# ST_LINK_V2-1.net
KiCad netlist of a schematic drawn in Altium Designer
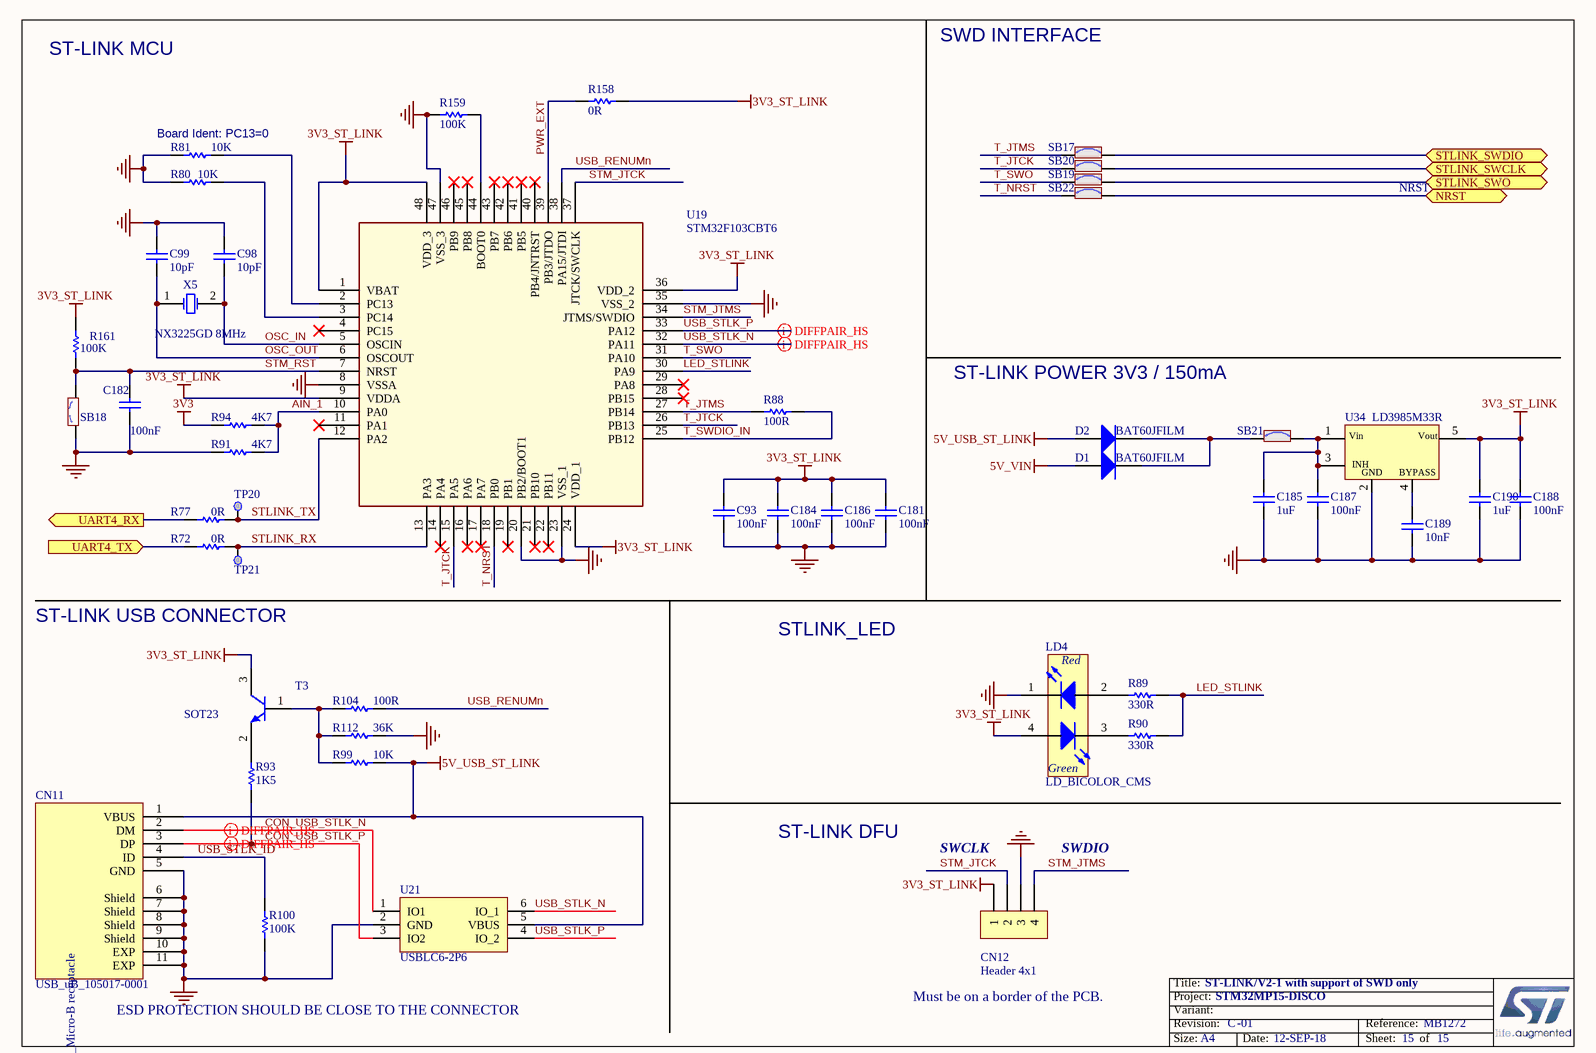
[diagram p0: ST_LINK_V2-1.SCHDOC]

(export (version "E")
  (design (tool "Eeschema 10.0.6"))
  (components
    (comp (ref "C93")
      (value "100nF")
      (footprint "C0402")
      (description "Capacitor,100nF,16V,X7R,10%,0402")
      (fields
        (field (name "INTERNAL_PART_NUMBER") "MCD-00006")
        (field (name "MANUFACTURER_PART_NUMBER") "CC0402KRX7R7BB104")
        (field (name "PROVIDED_BY") "SUBCO")
      )
      (libsource (lib "MCD_PARTS_database") (part "Capacitor"))
    )
    (comp (ref "C98")
      (value "10pF")
      (footprint "C0402")
      (description "Capacitor,10pF,50V,NPO,5%,0402")
      (fields
        (field (name "INTERNAL_PART_NUMBER") "MCD-00015")
        (field (name "MANUFACTURER_PART_NUMBER") "CC0402JRNPO9BN100")
        (field (name "PROVIDED_BY") "SUBCO")
      )
      (libsource (lib "MCD_PARTS_database") (part "Capacitor"))
    )
    (comp (ref "C99")
      (value "10pF")
      (footprint "C0402")
      (description "Capacitor,10pF,50V,NPO,5%,0402")
      (fields
        (field (name "INTERNAL_PART_NUMBER") "MCD-00015")
        (field (name "MANUFACTURER_PART_NUMBER") "CC0402JRNPO9BN100")
        (field (name "PROVIDED_BY") "SUBCO")
      )
      (libsource (lib "MCD_PARTS_database") (part "Capacitor"))
    )
    (comp (ref "C181")
      (value "100nF")
      (footprint "C0402")
      (description "Capacitor,100nF,16V,X7R,10%,0402")
      (fields
        (field (name "INTERNAL_PART_NUMBER") "MCD-00006")
        (field (name "MANUFACTURER_PART_NUMBER") "CC0402KRX7R7BB104")
        (field (name "PROVIDED_BY") "SUBCO")
      )
      (libsource (lib "MCD_PARTS_database") (part "Capacitor"))
    )
    (comp (ref "C182")
      (value "100nF")
      (footprint "C0402")
      (description "Capacitor,100nF,16V,X7R,10%,0402")
      (fields
        (field (name "INTERNAL_PART_NUMBER") "MCD-00006")
        (field (name "MANUFACTURER_PART_NUMBER") "CC0402KRX7R7BB104")
        (field (name "PROVIDED_BY") "SUBCO")
      )
      (libsource (lib "MCD_PARTS_database") (part "Capacitor"))
    )
    (comp (ref "C184")
      (value "100nF")
      (footprint "C0402")
      (description "Capacitor,100nF,16V,X7R,10%,0402")
      (fields
        (field (name "INTERNAL_PART_NUMBER") "MCD-00006")
        (field (name "MANUFACTURER_PART_NUMBER") "CC0402KRX7R7BB104")
        (field (name "PROVIDED_BY") "SUBCO")
      )
      (libsource (lib "MCD_PARTS_database") (part "Capacitor"))
    )
    (comp (ref "C185")
      (value "1uF")
      (footprint "C0603")
      (description "Capacitor,1uF,6V3,X5R,10%,0603")
      (fields
        (field (name "INTERNAL_PART_NUMBER") "MCD-00238")
        (field (name "MANUFACTURER_PART_NUMBER") "CC0603KRX5R5BB105")
        (field (name "PROVIDED_BY") "SUBCO")
      )
      (libsource (lib "MCD_PARTS_database") (part "Capacitor"))
    )
    (comp (ref "C186")
      (value "100nF")
      (footprint "C0402")
      (description "Capacitor,100nF,16V,X7R,10%,0402")
      (fields
        (field (name "INTERNAL_PART_NUMBER") "MCD-00006")
        (field (name "MANUFACTURER_PART_NUMBER") "CC0402KRX7R7BB104")
        (field (name "PROVIDED_BY") "SUBCO")
      )
      (libsource (lib "MCD_PARTS_database") (part "Capacitor"))
    )
    (comp (ref "C187")
      (value "100nF")
      (footprint "C0402")
      (description "Capacitor,100nF,16V,X7R,10%,0402")
      (fields
        (field (name "INTERNAL_PART_NUMBER") "MCD-00006")
        (field (name "MANUFACTURER_PART_NUMBER") "CC0402KRX7R7BB104")
        (field (name "PROVIDED_BY") "SUBCO")
      )
      (libsource (lib "MCD_PARTS_database") (part "Capacitor"))
    )
    (comp (ref "C188")
      (value "100nF")
      (footprint "C0402")
      (description "Capacitor,100nF,16V,X7R,10%,0402")
      (fields
        (field (name "INTERNAL_PART_NUMBER") "MCD-00006")
        (field (name "MANUFACTURER_PART_NUMBER") "CC0402KRX7R7BB104")
        (field (name "PROVIDED_BY") "SUBCO")
      )
      (libsource (lib "MCD_PARTS_database") (part "Capacitor"))
    )
    (comp (ref "C189")
      (value "10nF")
      (footprint "C0402")
      (description "Capacitor,10nF,16V,X7R,10%,0402")
      (fields
        (field (name "INTERNAL_PART_NUMBER") "MCD-00011")
        (field (name "MANUFACTURER_PART_NUMBER") "CC0402KRX7R7BB103")
        (field (name "PROVIDED_BY") "SUBCO")
      )
      (libsource (lib "MCD_PARTS_database") (part "Capacitor"))
    )
    (comp (ref "C190")
      (value "1uF")
      (footprint "C0603")
      (description "Capacitor,1uF,6V3,X5R,10%,0603")
      (fields
        (field (name "INTERNAL_PART_NUMBER") "MCD-00238")
        (field (name "MANUFACTURER_PART_NUMBER") "CC0603KRX5R5BB105")
        (field (name "PROVIDED_BY") "SUBCO")
      )
      (libsource (lib "MCD_PARTS_database") (part "Capacitor"))
    )
    (comp (ref "CN11")
      (value "USB_uB_105017-0001")
      (footprint "CON_USBMICROB_MOLEX_105017-0001_H2P90")
      (description "USB-MICRO-B, 0.65mm, RA, SMT, Bottom Mount,")
      (fields
        (field (name "INTERNAL_PART_NUMBER") "MCD-00028")
        (field (name "MANUFACTURER_PART_NUMBER") "1050170001")
        (field (name "PROVIDED_BY") "SUBCO")
      )
      (libsource (lib "MCD_PARTS_database") (part "USB_uB_105017.0001"))
    )
    (comp (ref "CN12")
      (value "Header 4x1")
      (footprint "CON_SAMTEC_TSW-104-07-G-S")
      (description "Header, 4x1, 2,54mm, VR, TH, Height 5.84mm/2.54mm")
      (fields
        (field (name "INTERNAL_PART_NUMBER") "MCD-00029")
        (field (name "MANUFACTURER_PART_NUMBER") "TSW-104-07-x-S")
        (field (name "PROVIDED_BY") "SUBCO")
      )
      (libsource (lib "MCD_PARTS_database") (part "Header 4x1"))
    )
    (comp (ref "D1")
      (value "BAT60JFILM")
      (footprint "DIO_SOD323")
      (fields
        (field (name "INTERNAL_PART_NUMBER") "MCD-00034")
        (field (name "MANUFACTURER") "STMICROELECTRONICS")
        (field (name "BMS_PART_NUMBER") "9151097")
        (field (name "PROVIDED_BY") "SUBCO with ST control")
      )
      (libsource (lib "MCD_PARTS_database") (part "BAT60JFILM"))
    )
    (comp (ref "D2")
      (value "BAT60JFILM")
      (footprint "DIO_SOD323")
      (fields
        (field (name "INTERNAL_PART_NUMBER") "MCD-00034")
        (field (name "MANUFACTURER") "STMICROELECTRONICS")
        (field (name "BMS_PART_NUMBER") "9151097")
        (field (name "PROVIDED_BY") "SUBCO with ST control")
      )
      (libsource (lib "MCD_PARTS_database") (part "BAT60JFILM"))
    )
    (comp (ref "LD4")
      (value "LD_BICOLOR_CMS")
      (footprint "LED_BI-GR_HSMF-A201-A00J1")
      (description "LED Bicolor")
      (fields
        (field (name "INTERNAL_PART_NUMBER") "MCD-00051")
        (field (name "MANUFACTURER_PART_NUMBER") "HSMF-A201-A00J1")
        (field (name "PROVIDED_BY") "SUBCO")
      )
      (libsource (lib "MCD_PARTS_database") (part "LD_BICOLOR_CMS"))
    )
    (comp (ref "R72")
      (value "0R")
      (footprint "R0402")
      (description "Resistor,0R,0402,5%,1/16W")
      (fields
        (field (name "INTERNAL_PART_NUMBER") "MCD-00052")
        (field (name "MANUFACTURER_PART_NUMBER") "RC0402JR-070RL")
        (field (name "PROVIDED_BY") "SUBCO")
      )
      (libsource (lib "MCD_PARTS_database") (part "Resistor"))
    )
    (comp (ref "R77")
      (value "0R")
      (footprint "R0402")
      (description "Resistor,0R,0402,5%,1/16W")
      (fields
        (field (name "INTERNAL_PART_NUMBER") "MCD-00052")
        (field (name "MANUFACTURER_PART_NUMBER") "RC0402JR-070RL")
        (field (name "PROVIDED_BY") "SUBCO")
      )
      (libsource (lib "MCD_PARTS_database") (part "Resistor"))
    )
    (comp (ref "R80")
      (value "10K")
      (footprint "R0402")
      (description "Resistor,10K,0402,1%,1/16W")
      (fields
        (field (name "INTERNAL_PART_NUMBER") "MCD-00053")
        (field (name "MANUFACTURER_PART_NUMBER") "RC0402FR-0710KL")
        (field (name "PROVIDED_BY") "SUBCO")
      )
      (libsource (lib "MCD_PARTS_database") (part "Resistor"))
    )
    (comp (ref "R81")
      (value "10K")
      (footprint "R0402")
      (description "Resistor,10K,0402,1%,1/16W")
      (fields
        (field (name "INTERNAL_PART_NUMBER") "MCD-00053")
        (field (name "MANUFACTURER_PART_NUMBER") "RC0402FR-0710KL")
        (field (name "PROVIDED_BY") "SUBCO")
      )
      (libsource (lib "MCD_PARTS_database") (part "Resistor"))
    )
    (comp (ref "R88")
      (value "100R")
      (footprint "R0402")
      (description "Resistor,100R,0402,1%,1/16W")
      (fields
        (field (name "INTERNAL_PART_NUMBER") "MCD-00067")
        (field (name "MANUFACTURER_PART_NUMBER") "RC0402FR-07100RL")
        (field (name "PROVIDED_BY") "SUBCO")
      )
      (libsource (lib "MCD_PARTS_database") (part "Resistor"))
    )
    (comp (ref "R89")
      (value "330R")
      (footprint "R0402")
      (description "Resistor,330R,0402,1%,1/16W")
      (fields
        (field (name "INTERNAL_PART_NUMBER") "MCD-00062")
        (field (name "MANUFACTURER_PART_NUMBER") "RC0402FR-07330RL")
        (field (name "PROVIDED_BY") "SUBCO")
      )
      (libsource (lib "MCD_PARTS_database") (part "Resistor"))
    )
    (comp (ref "R90")
      (value "330R")
      (footprint "R0402")
      (description "Resistor,330R,0402,1%,1/16W")
      (fields
        (field (name "INTERNAL_PART_NUMBER") "MCD-00062")
        (field (name "MANUFACTURER_PART_NUMBER") "RC0402FR-07330RL")
        (field (name "PROVIDED_BY") "SUBCO")
      )
      (libsource (lib "MCD_PARTS_database") (part "Resistor"))
    )
    (comp (ref "R91")
      (value "4K7")
      (footprint "R0402")
      (description "Resistor,4K7,0402,1%,1/16W")
      (fields
        (field (name "INTERNAL_PART_NUMBER") "MCD-00065")
        (field (name "MANUFACTURER_PART_NUMBER") "RC0402FR-074K7L")
        (field (name "PROVIDED_BY") "SUBCO")
      )
      (libsource (lib "MCD_PARTS_database") (part "Resistor"))
    )
    (comp (ref "R93")
      (value "1K5")
      (footprint "R0402")
      (description "Resistor,1K5,0402,1%,1/16W")
      (fields
        (field (name "INTERNAL_PART_NUMBER") "MCD-00068")
        (field (name "MANUFACTURER_PART_NUMBER") "RC0402FR-071K5L")
        (field (name "PROVIDED_BY") "SUBCO")
      )
      (libsource (lib "MCD_PARTS_database") (part "Resistor"))
    )
    (comp (ref "R94")
      (value "4K7")
      (footprint "R0402")
      (description "Resistor,4K7,0402,1%,1/16W")
      (fields
        (field (name "INTERNAL_PART_NUMBER") "MCD-00065")
        (field (name "MANUFACTURER_PART_NUMBER") "RC0402FR-074K7L")
        (field (name "PROVIDED_BY") "SUBCO")
      )
      (libsource (lib "MCD_PARTS_database") (part "Resistor"))
    )
    (comp (ref "R99")
      (value "10K")
      (footprint "R0402")
      (description "Resistor,10K,0402,1%,1/16W")
      (fields
        (field (name "INTERNAL_PART_NUMBER") "MCD-00053")
        (field (name "MANUFACTURER_PART_NUMBER") "RC0402FR-0710KL")
        (field (name "PROVIDED_BY") "SUBCO")
      )
      (libsource (lib "MCD_PARTS_database") (part "Resistor"))
    )
    (comp (ref "R100")
      (value "100K")
      (footprint "R0402")
      (description "Resistor,100K,0402,1%,1/16W")
      (fields
        (field (name "INTERNAL_PART_NUMBER") "MCD-00059")
        (field (name "MANUFACTURER_PART_NUMBER") "RC0402FR-07100KL")
        (field (name "PROVIDED_BY") "SUBCO")
      )
      (libsource (lib "MCD_PARTS_database") (part "Resistor"))
    )
    (comp (ref "R104")
      (value "100R")
      (footprint "R0402")
      (description "Resistor,100R,0402,1%,1/16W")
      (fields
        (field (name "INTERNAL_PART_NUMBER") "MCD-00067")
        (field (name "MANUFACTURER_PART_NUMBER") "RC0402FR-07100RL")
        (field (name "PROVIDED_BY") "SUBCO")
      )
      (libsource (lib "MCD_PARTS_database") (part "Resistor"))
    )
    (comp (ref "R112")
      (value "36K")
      (footprint "R0402")
      (description "Resistor,36K,0402,1%,1/16W")
      (fields
        (field (name "INTERNAL_PART_NUMBER") "MCD-00069")
        (field (name "MANUFACTURER_PART_NUMBER") "RC0402FR-0736KL")
        (field (name "PROVIDED_BY") "SUBCO")
      )
      (libsource (lib "MCD_PARTS_database") (part "Resistor"))
    )
    (comp (ref "R158")
      (value "0R")
      (footprint "R0402")
      (description "Resistor,0R,0402,5%,1/16W")
      (fields
        (field (name "INTERNAL_PART_NUMBER") "MCD-00052")
        (field (name "MANUFACTURER_PART_NUMBER") "RC0402JR-070RL")
        (field (name "PROVIDED_BY") "SUBCO")
      )
      (libsource (lib "MCD_PARTS_database") (part "Resistor"))
    )
    (comp (ref "R159")
      (value "100K")
      (footprint "R0402")
      (description "Resistor,100K,0402,1%,1/16W")
      (fields
        (field (name "INTERNAL_PART_NUMBER") "MCD-00059")
        (field (name "MANUFACTURER_PART_NUMBER") "RC0402FR-07100KL")
        (field (name "PROVIDED_BY") "SUBCO")
      )
      (libsource (lib "MCD_PARTS_database") (part "Resistor"))
    )
    (comp (ref "R161")
      (value "100K")
      (footprint "R0402")
      (description "Resistor,100K,0402,1%,1/16W")
      (fields
        (field (name "INTERNAL_PART_NUMBER") "MCD-00059")
        (field (name "MANUFACTURER_PART_NUMBER") "RC0402FR-07100KL")
        (field (name "PROVIDED_BY") "SUBCO")
      )
      (libsource (lib "MCD_PARTS_database") (part "Resistor"))
    )
    (comp (ref "SB17")
      (value "~")
      (footprint "SOLDER-BRIDGE_R0603-0R")
      (description "Solder Bridge ON")
      (fields
        (field (name "INTERNAL_PART_NUMBER") "MCD-00071")
        (field (name "MANUFACTURER") "YAGEO")
        (field (name "PROVIDED_BY") "SUBCO")
      )
      (libsource (lib "MCD_PARTS_database") (part "SB_ON"))
    )
    (comp (ref "SB18")
      (value "~")
      (footprint "SOLDER-BRIDGE_R0603-0R")
      (description "Solder Bridge OFF")
      (fields
        (field (name "INTERNAL_PART_NUMBER") "MCD-00072")
        (field (name "MANUFACTURER") "YAGEO")
        (field (name "PROVIDED_BY") "SUBCO")
      )
      (libsource (lib "MCD_PARTS_database") (part "SB_OFF"))
    )
    (comp (ref "SB19")
      (value "~")
      (footprint "SOLDER-BRIDGE_R0603-0R")
      (description "Solder Bridge ON")
      (fields
        (field (name "INTERNAL_PART_NUMBER") "MCD-00071")
        (field (name "MANUFACTURER") "YAGEO")
        (field (name "PROVIDED_BY") "SUBCO")
      )
      (libsource (lib "MCD_PARTS_database") (part "SB_ON"))
    )
    (comp (ref "SB20")
      (value "~")
      (footprint "SOLDER-BRIDGE_R0603-0R")
      (description "Solder Bridge ON")
      (fields
        (field (name "INTERNAL_PART_NUMBER") "MCD-00071")
        (field (name "MANUFACTURER") "YAGEO")
        (field (name "PROVIDED_BY") "SUBCO")
      )
      (libsource (lib "MCD_PARTS_database") (part "SB_ON"))
    )
    (comp (ref "SB21")
      (value "~")
      (footprint "SOLDER-BRIDGE_R0603-0R")
      (description "Solder Bridge ON")
      (fields
        (field (name "INTERNAL_PART_NUMBER") "MCD-00071")
        (field (name "MANUFACTURER") "YAGEO")
        (field (name "PROVIDED_BY") "SUBCO")
      )
      (libsource (lib "MCD_PARTS_database") (part "SB_ON"))
    )
    (comp (ref "SB22")
      (value "~")
      (footprint "SOLDER-BRIDGE_R0603-0R")
      (description "Solder Bridge ON")
      (fields
        (field (name "INTERNAL_PART_NUMBER") "MCD-00071")
        (field (name "MANUFACTURER") "YAGEO")
        (field (name "PROVIDED_BY") "SUBCO")
      )
      (libsource (lib "MCD_PARTS_database") (part "SB_ON"))
    )
    (comp (ref "T3")
      (value "SOT23")
      (footprint "NPN_SOT23")
      (description "NPN Bipolar Transistor")
      (fields
        (field (name "INTERNAL_PART_NUMBER") "MCD-00073")
        (field (name "MANUFACTURER_PART_NUMBER") "BSR14")
        (field (name "PROVIDED_BY") "SUBCO")
      )
      (libsource (lib "MCD_PARTS_database") (part "9013-SOT23"))
    )
    (comp (ref "TP20")
      (value "Test Point")
      (footprint "TP_SMD_1MM")
      (description "Test Point 1mm")
      (fields
        (field (name "INTERNAL_PART_NUMBER") "MCD-00074")
        (field (name "MANUFACTURER_PART_NUMBER") "n/a")
      )
      (libsource (lib "") (part "Test Point_1"))
    )
    (comp (ref "TP21")
      (value "Test Point")
      (footprint "TP_SMD_1MM")
      (description "Test Point 1mm")
      (fields
        (field (name "INTERNAL_PART_NUMBER") "MCD-00074")
        (field (name "MANUFACTURER_PART_NUMBER") "n/a")
      )
      (libsource (lib "MCD_PARTS_database") (part "Test Point"))
    )
    (comp (ref "U19")
      (value "STM32F103CBT6")
      (footprint "ICC_LQFP48_7X7_P050")
      (description "Medium-density performance line ARM-based 32-bit MCU with 128KB Flash")
      (fields
        (field (name "INTERNAL_PART_NUMBER") "MCD-00085")
        (field (name "MANUFACTURER") "STMICROELECTRONICS")
        (field (name "PROVIDED_BY") "SUBCO with ST control")
      )
      (libsource (lib "MCD_PARTS_database") (part "STM32F103CBT6"))
    )
    (comp (ref "U21")
      (value "USBLC6-2P6")
      (footprint "ESD_SOT666")
      (description "USB OTG FS ESD protection")
      (fields
        (field (name "INTERNAL_PART_NUMBER") "MCD-00169")
        (field (name "MANUFACTURER") "STMICROELECTRONICS")
        (field (name "PROVIDED_BY") "SUBCO with ST control")
      )
      (libsource (lib "MCD_PARTS_database") (part "USBLC6-2P6"))
    )
    (comp (ref "U34")
      (value "LD3985M33R")
      (footprint "REG_SOT23-5L")
      (description "Ultra low drop-low noise BiCMOS voltage, regulators low ESR capacitors compatible")
      (fields
        (field (name "INTERNAL_PART_NUMBER") "MCD-00086")
        (field (name "MANUFACTURER") "STMICROELECTRONICS")
        (field (name "PROVIDED_BY") "SUBCO with ST control")
      )
      (libsource (lib "MCD_PARTS_database") (part "LD3985M33R"))
    )
    (comp (ref "X5")
      (value "NX3225GD 8MHz")
      (footprint "CRY_NX3225GD_2P")
      (description "Crystal 8Mhz, 8pF, -+50PPM, SMD")
      (fields
        (field (name "INTERNAL_PART_NUMBER") "MCD-00092")
        (field (name "MANUFACTURER_PART_NUMBER") "NX3225GD 8MHz EXS00A-CG04874")
        (field (name "PROVIDED_BY") "SUBCO")
      )
      (libsource (lib "MCD_PARTS_database") (part "XTAL_8M_NX3225GD"))
    )
  )
  (nets
    (net (code "1") (name "/AIN_1") (class "Default")
      (node (ref "R91") (pin "2") (pinfunction "2_2") (pintype "passive"))
      (node (ref "R94") (pin "2") (pinfunction "2_2") (pintype "passive"))
      (node (ref "U19") (pin "10") (pinfunction "PA0_10") (pintype "passive"))
    )
    (net (code "2") (name "/CON_USB_STLK_N") (class "Default")
      (node (ref "CN11") (pin "2") (pinfunction "DM_2") (pintype "passive"))
      (node (ref "U21") (pin "1") (pinfunction "IO1_1") (pintype "passive"))
    )
    (net (code "3") (name "/CON_USB_STLK_P") (class "Default")
      (node (ref "CN11") (pin "3") (pinfunction "DP_3") (pintype "passive"))
      (node (ref "R93") (pin "1") (pinfunction "1_1") (pintype "passive"))
      (node (ref "U21") (pin "3") (pinfunction "IO2_3") (pintype "passive"))
    )
    (net (code "4") (name "/LED_STLINK") (class "Default")
      (node (ref "R89") (pin "2") (pinfunction "2_2") (pintype "passive"))
      (node (ref "R90") (pin "2") (pinfunction "2_2") (pintype "passive"))
      (node (ref "U19") (pin "30") (pinfunction "PA9_30") (pintype "passive"))
    )
    (net (code "5") (name "/NRST") (class "Default")
      (node (ref "SB22") (pin "2") (pinfunction "2_2") (pintype "passive"))
    )
    (net (code "6") (name "/OSC_IN") (class "Default")
      (node (ref "C98") (pin "1") (pinfunction "1_1") (pintype "passive"))
      (node (ref "U19") (pin "5") (pinfunction "OSCIN_5") (pintype "passive"))
      (node (ref "X5") (pin "2") (pinfunction "OSC2_2") (pintype "passive"))
    )
    (net (code "7") (name "/OSC_OUT") (class "Default")
      (node (ref "C99") (pin "1") (pinfunction "1_1") (pintype "passive"))
      (node (ref "U19") (pin "6") (pinfunction "OSCOUT_6") (pintype "passive"))
      (node (ref "X5") (pin "1") (pinfunction "OSC1_1") (pintype "passive"))
    )
    (net (code "8") (name "/PWR_EXT") (class "Default")
      (node (ref "R158") (pin "1") (pinfunction "1_1") (pintype "passive"))
      (node (ref "U19") (pin "39") (pinfunction "PB3/JTDO_39") (pintype "passive"))
    )
    (net (code "9") (name "/STLINK_RX") (class "Default")
      (node (ref "R72") (pin "2") (pinfunction "2_2") (pintype "passive"))
      (node (ref "TP21") (pin "1") (pinfunction "1_1") (pintype "passive"))
      (node (ref "U19") (pin "13") (pinfunction "PA3_13") (pintype "passive"))
    )
    (net (code "10") (name "/STLINK_SWCLK") (class "Default")
      (node (ref "SB20") (pin "2") (pinfunction "2_2") (pintype "passive"))
    )
    (net (code "11") (name "/STLINK_SWDIO") (class "Default")
      (node (ref "SB17") (pin "2") (pinfunction "2_2") (pintype "passive"))
    )
    (net (code "12") (name "/STLINK_SWO") (class "Default")
      (node (ref "SB19") (pin "2") (pinfunction "2_2") (pintype "passive"))
    )
    (net (code "13") (name "/STLINK_TX") (class "Default")
      (node (ref "R77") (pin "1") (pinfunction "1_1") (pintype "passive"))
      (node (ref "TP20") (pin "1") (pinfunction "1_1") (pintype "passive"))
      (node (ref "U19") (pin "12") (pinfunction "PA2_12") (pintype "passive"))
    )
    (net (code "14") (name "/STM_JTCK") (class "Default")
      (node (ref "CN12") (pin "2") (pinfunction "2_2") (pintype "passive"))
      (node (ref "U19") (pin "37") (pinfunction "JTCK/SWCLK_37") (pintype "passive"))
    )
    (net (code "15") (name "/STM_JTMS") (class "Default")
      (node (ref "CN12") (pin "4") (pinfunction "4_4") (pintype "passive"))
      (node (ref "U19") (pin "34") (pinfunction "JTMS/SWDIO_34") (pintype "passive"))
    )
    (net (code "16") (name "/STM_RST") (class "Default")
      (node (ref "C182") (pin "2") (pinfunction "2_2") (pintype "passive"))
      (node (ref "R161") (pin "1") (pinfunction "1_1") (pintype "passive"))
      (node (ref "SB18") (pin "2") (pinfunction "2_2") (pintype "passive"))
      (node (ref "U19") (pin "7") (pinfunction "NRST_7") (pintype "passive"))
    )
    (net (code "17") (name "/T_JTCK") (class "Default")
      (node (ref "SB20") (pin "1") (pinfunction "1_1") (pintype "passive"))
      (node (ref "U19") (pin "15") (pinfunction "PA5_15") (pintype "passive"))
      (node (ref "U19") (pin "26") (pinfunction "PB13_26") (pintype "passive"))
    )
    (net (code "18") (name "/T_JTMS") (class "Default")
      (node (ref "R88") (pin "1") (pinfunction "1_1") (pintype "passive"))
      (node (ref "SB17") (pin "1") (pinfunction "1_1") (pintype "passive"))
      (node (ref "U19") (pin "27") (pinfunction "PB14_27") (pintype "passive"))
    )
    (net (code "19") (name "/T_NRST") (class "Default")
      (node (ref "SB22") (pin "1") (pinfunction "1_1") (pintype "passive"))
      (node (ref "U19") (pin "18") (pinfunction "PB0_18") (pintype "passive"))
    )
    (net (code "20") (name "/T_SWDIO_IN") (class "Default")
      (node (ref "R88") (pin "2") (pinfunction "2_2") (pintype "passive"))
      (node (ref "U19") (pin "25") (pinfunction "PB12_25") (pintype "passive"))
    )
    (net (code "21") (name "/T_SWO") (class "Default")
      (node (ref "SB19") (pin "1") (pinfunction "1_1") (pintype "passive"))
      (node (ref "U19") (pin "31") (pinfunction "PA10_31") (pintype "passive"))
    )
    (net (code "22") (name "/UART4_RX") (class "Default")
      (node (ref "R77") (pin "2") (pinfunction "2_2") (pintype "passive"))
    )
    (net (code "23") (name "/UART4_TX") (class "Default")
      (node (ref "R72") (pin "1") (pinfunction "1_1") (pintype "passive"))
    )
    (net (code "24") (name "/USB_RENUMn") (class "Default")
      (node (ref "R104") (pin "2") (pinfunction "2_2") (pintype "passive"))
      (node (ref "U19") (pin "38") (pinfunction "PA15/JTDI_38") (pintype "passive"))
    )
    (net (code "25") (name "/USB_STLK_ID") (class "Default")
      (node (ref "CN11") (pin "4") (pinfunction "ID_4") (pintype "passive"))
      (node (ref "R100") (pin "2") (pinfunction "2_2") (pintype "passive"))
    )
    (net (code "26") (name "/USB_STLK_N") (class "Default")
      (node (ref "U19") (pin "32") (pinfunction "PA11_32") (pintype "passive"))
      (node (ref "U21") (pin "6") (pinfunction "IO_1_6") (pintype "passive"))
    )
    (net (code "27") (name "/USB_STLK_P") (class "Default")
      (node (ref "U19") (pin "33") (pinfunction "PA12_33") (pintype "passive"))
      (node (ref "U21") (pin "4") (pinfunction "IO_2_4") (pintype "passive"))
    )
    (net (code "28") (name "3V3") (class "Default")
      (node (ref "R94") (pin "1") (pinfunction "1_1") (pintype "passive"))
    )
    (net (code "29") (name "3V3_ST_LINK") (class "Default")
      (node (ref "C181") (pin "2") (pinfunction "2_2") (pintype "passive"))
      (node (ref "C184") (pin "2") (pinfunction "2_2") (pintype "passive"))
      (node (ref "C186") (pin "2") (pinfunction "2_2") (pintype "passive"))
      (node (ref "C188") (pin "2") (pinfunction "2_2") (pintype "passive"))
      (node (ref "C190") (pin "2") (pinfunction "2_2") (pintype "passive"))
      (node (ref "C93") (pin "2") (pinfunction "2_2") (pintype "passive"))
      (node (ref "CN12") (pin "1") (pinfunction "1_1") (pintype "passive"))
      (node (ref "LD4") (pin "4") (pinfunction "YellowGreen_anode_4") (pintype "passive"))
      (node (ref "R158") (pin "2") (pinfunction "2_2") (pintype "passive"))
      (node (ref "R161") (pin "2") (pinfunction "2_2") (pintype "passive"))
      (node (ref "T3") (pin "3") (pinfunction "C_3") (pintype "passive"))
      (node (ref "U19") (pin "1") (pinfunction "VBAT_1") (pintype "passive"))
      (node (ref "U19") (pin "24") (pinfunction "VDD_1_24") (pintype "passive"))
      (node (ref "U19") (pin "36") (pinfunction "VDD_2_36") (pintype "passive"))
      (node (ref "U19") (pin "48") (pinfunction "VDD_3_48") (pintype "passive"))
      (node (ref "U19") (pin "9") (pinfunction "VDDA_9") (pintype "passive"))
      (node (ref "U34") (pin "5") (pinfunction "Vout_5") (pintype "passive"))
    )
    (net (code "30") (name "5V_USB_ST_LINK") (class "Default")
      (node (ref "CN11") (pin "1") (pinfunction "VBUS_1") (pintype "passive"))
      (node (ref "D2") (pin "1") (pinfunction "A_1") (pintype "passive"))
      (node (ref "R99") (pin "1") (pinfunction "1_1") (pintype "passive"))
      (node (ref "U21") (pin "5") (pinfunction "VBUS_5") (pintype "passive"))
    )
    (net (code "31") (name "5V_VIN") (class "Default")
      (node (ref "D1") (pin "1") (pinfunction "A_1") (pintype "passive"))
    )
    (net (code "32") (name "GND") (class "Default")
      (node (ref "C181") (pin "1") (pinfunction "1_1") (pintype "passive"))
      (node (ref "C182") (pin "1") (pinfunction "1_1") (pintype "passive"))
      (node (ref "C184") (pin "1") (pinfunction "1_1") (pintype "passive"))
      (node (ref "C185") (pin "2") (pinfunction "2_2") (pintype "passive"))
      (node (ref "C186") (pin "1") (pinfunction "1_1") (pintype "passive"))
      (node (ref "C187") (pin "1") (pinfunction "1_1") (pintype "passive"))
      (node (ref "C188") (pin "1") (pinfunction "1_1") (pintype "passive"))
      (node (ref "C189") (pin "1") (pinfunction "1_1") (pintype "passive"))
      (node (ref "C190") (pin "1") (pinfunction "1_1") (pintype "passive"))
      (node (ref "C93") (pin "1") (pinfunction "1_1") (pintype "passive"))
      (node (ref "C98") (pin "2") (pinfunction "2_2") (pintype "passive"))
      (node (ref "C99") (pin "2") (pinfunction "2_2") (pintype "passive"))
      (node (ref "CN11") (pin "10") (pinfunction "EXP_10") (pintype "passive"))
      (node (ref "CN11") (pin "11") (pinfunction "EXP_11") (pintype "passive"))
      (node (ref "CN11") (pin "5") (pinfunction "GND_5") (pintype "passive"))
      (node (ref "CN11") (pin "6") (pinfunction "Shield_6") (pintype "passive"))
      (node (ref "CN11") (pin "7") (pinfunction "Shield_7") (pintype "passive"))
      (node (ref "CN11") (pin "8") (pinfunction "Shield_8") (pintype "passive"))
      (node (ref "CN11") (pin "9") (pinfunction "Shield_9") (pintype "passive"))
      (node (ref "CN12") (pin "3") (pinfunction "3_3") (pintype "passive"))
      (node (ref "LD4") (pin "1") (pinfunction "RED_cathode_1") (pintype "passive"))
      (node (ref "R100") (pin "1") (pinfunction "1_1") (pintype "passive"))
      (node (ref "R112") (pin "1") (pinfunction "1_1") (pintype "passive"))
      (node (ref "R159") (pin "1") (pinfunction "1_1") (pintype "passive"))
      (node (ref "R80") (pin "1") (pinfunction "1_1") (pintype "passive"))
      (node (ref "R81") (pin "2") (pinfunction "2_2") (pintype "passive"))
      (node (ref "R91") (pin "1") (pinfunction "1_1") (pintype "passive"))
      (node (ref "SB18") (pin "1") (pinfunction "1_1") (pintype "passive"))
      (node (ref "U19") (pin "20") (pinfunction "PB2/BOOT1_20") (pintype "passive"))
      (node (ref "U19") (pin "23") (pinfunction "VSS_1_23") (pintype "passive"))
      (node (ref "U19") (pin "35") (pinfunction "VSS_2_35") (pintype "passive"))
      (node (ref "U19") (pin "47") (pinfunction "VSS_3_47") (pintype "passive"))
      (node (ref "U19") (pin "8") (pinfunction "VSSA_8") (pintype "passive"))
      (node (ref "U21") (pin "2") (pinfunction "GND_2") (pintype "passive"))
      (node (ref "U34") (pin "2") (pinfunction "GND_2") (pintype "passive"))
    )
    (net (code "33") (name "Net-(D1-K)") (class "Default")
      (node (ref "D1") (pin "2") (pinfunction "K_2") (pintype "passive"))
      (node (ref "D2") (pin "2") (pinfunction "K_2") (pintype "passive"))
      (node (ref "SB21") (pin "1") (pinfunction "1_1") (pintype "passive"))
    )
    (net (code "34") (name "Net-(LD4-Red_anode)") (class "Default")
      (node (ref "LD4") (pin "2") (pinfunction "Red_anode_2") (pintype "passive"))
      (node (ref "R89") (pin "1") (pinfunction "1_1") (pintype "passive"))
    )
    (net (code "35") (name "Net-(LD4-YellowGreen_cathode)") (class "Default")
      (node (ref "LD4") (pin "3") (pinfunction "YellowGreen_cathode_3") (pintype "passive"))
      (node (ref "R90") (pin "1") (pinfunction "1_1") (pintype "passive"))
    )
    (net (code "36") (name "Net-(T3-B)") (class "Default")
      (node (ref "R104") (pin "1") (pinfunction "1_1") (pintype "passive"))
      (node (ref "R112") (pin "2") (pinfunction "2_2") (pintype "passive"))
      (node (ref "R99") (pin "2") (pinfunction "2_2") (pintype "passive"))
      (node (ref "T3") (pin "1") (pinfunction "B_1") (pintype "passive"))
    )
    (net (code "37") (name "Net-(T3-E)") (class "Default")
      (node (ref "R93") (pin "2") (pinfunction "2_2") (pintype "passive"))
      (node (ref "T3") (pin "2") (pinfunction "E_2") (pintype "passive"))
    )
    (net (code "38") (name "Net-(U19-BOOT0)") (class "Default")
      (node (ref "R159") (pin "2") (pinfunction "2_2") (pintype "passive"))
      (node (ref "U19") (pin "44") (pinfunction "BOOT0_44") (pintype "passive"))
    )
    (net (code "39") (name "Net-(U19-PC13)") (class "Default")
      (node (ref "R81") (pin "1") (pinfunction "1_1") (pintype "passive"))
      (node (ref "U19") (pin "2") (pinfunction "PC13_2") (pintype "passive"))
    )
    (net (code "40") (name "Net-(U19-PC14)") (class "Default")
      (node (ref "R80") (pin "2") (pinfunction "2_2") (pintype "passive"))
      (node (ref "U19") (pin "3") (pinfunction "PC14_3") (pintype "passive"))
    )
    (net (code "41") (name "Net-(U34-BYPASS)") (class "Default")
      (node (ref "C189") (pin "2") (pinfunction "2_2") (pintype "passive"))
      (node (ref "U34") (pin "4") (pinfunction "BYPASS_4") (pintype "passive"))
    )
    (net (code "42") (name "Net-(U34-CE)") (class "Default")
      (node (ref "C185") (pin "1") (pinfunction "1_1") (pintype "passive"))
      (node (ref "C187") (pin "2") (pinfunction "2_2") (pintype "passive"))
      (node (ref "SB21") (pin "2") (pinfunction "2_2") (pintype "passive"))
      (node (ref "U34") (pin "1") (pinfunction "Vin_1") (pintype "passive"))
      (node (ref "U34") (pin "3") (pinfunction "CE_3") (pintype "passive"))
    )
    (net (code "43") (name "unconnected-(U19-PA1-Pad11)") (class "Default")
      (node (ref "U19") (pin "11") (pinfunction "PA1_11") (pintype "passive+no_connect"))
    )
    (net (code "44") (name "unconnected-(U19-PA4-Pad14)") (class "Default")
      (node (ref "U19") (pin "14") (pinfunction "PA4_14") (pintype "passive+no_connect"))
    )
    (net (code "45") (name "unconnected-(U19-PA6-Pad16)") (class "Default")
      (node (ref "U19") (pin "16") (pinfunction "PA6_16") (pintype "passive+no_connect"))
    )
    (net (code "46") (name "unconnected-(U19-PA7-Pad17)") (class "Default")
      (node (ref "U19") (pin "17") (pinfunction "PA7_17") (pintype "passive+no_connect"))
    )
    (net (code "47") (name "unconnected-(U19-PA8-Pad29)") (class "Default")
      (node (ref "U19") (pin "29") (pinfunction "PA8_29") (pintype "passive+no_connect"))
    )
    (net (code "48") (name "unconnected-(U19-PB1-Pad19)") (class "Default")
      (node (ref "U19") (pin "19") (pinfunction "PB1_19") (pintype "passive+no_connect"))
    )
    (net (code "49") (name "unconnected-(U19-PB4{slash}JNTRST-Pad40)") (class "Default")
      (node (ref "U19") (pin "40") (pinfunction "PB4/JNTRST_40") (pintype "passive+no_connect"))
    )
    (net (code "50") (name "unconnected-(U19-PB5-Pad41)") (class "Default")
      (node (ref "U19") (pin "41") (pinfunction "PB5_41") (pintype "passive+no_connect"))
    )
    (net (code "51") (name "unconnected-(U19-PB6-Pad42)") (class "Default")
      (node (ref "U19") (pin "42") (pinfunction "PB6_42") (pintype "passive+no_connect"))
    )
    (net (code "52") (name "unconnected-(U19-PB7-Pad43)") (class "Default")
      (node (ref "U19") (pin "43") (pinfunction "PB7_43") (pintype "passive+no_connect"))
    )
    (net (code "53") (name "unconnected-(U19-PB8-Pad45)") (class "Default")
      (node (ref "U19") (pin "45") (pinfunction "PB8_45") (pintype "passive+no_connect"))
    )
    (net (code "54") (name "unconnected-(U19-PB9-Pad46)") (class "Default")
      (node (ref "U19") (pin "46") (pinfunction "PB9_46") (pintype "passive+no_connect"))
    )
    (net (code "55") (name "unconnected-(U19-PB10-Pad21)") (class "Default")
      (node (ref "U19") (pin "21") (pinfunction "PB10_21") (pintype "passive+no_connect"))
    )
    (net (code "56") (name "unconnected-(U19-PB11-Pad22)") (class "Default")
      (node (ref "U19") (pin "22") (pinfunction "PB11_22") (pintype "passive+no_connect"))
    )
    (net (code "57") (name "unconnected-(U19-PB15-Pad28)") (class "Default")
      (node (ref "U19") (pin "28") (pinfunction "PB15_28") (pintype "passive+no_connect"))
    )
    (net (code "58") (name "unconnected-(U19-PC15-Pad4)") (class "Default")
      (node (ref "U19") (pin "4") (pinfunction "PC15_4") (pintype "passive+no_connect"))
    )
  )
)
